# bigbro.net
KiCad netlist of a schematic drawn in EAGLE
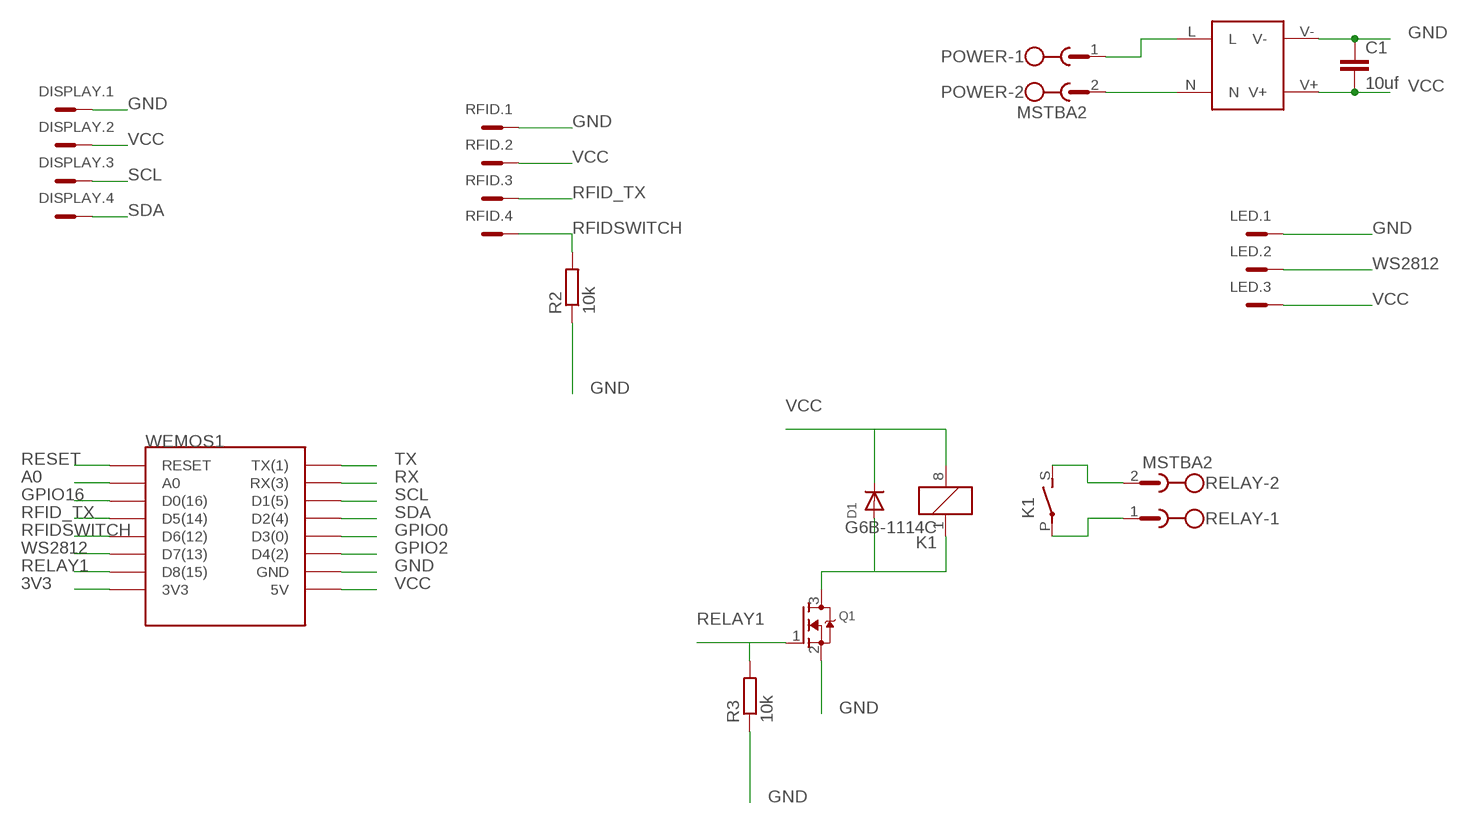
[diagram p0: schematic, sheet 1]

(export (version "E")
  (design (tool "Eeschema 10.0.6"))
  (components
    (comp (ref "C1")
      (value "10uf")
      (footprint "eagle-import:C0805")
      (libsource (lib "eagle-import") (part "C-EUC0805"))
    )
    (comp (ref "D1")
      (value "DIODESMA")
      (footprint "eagle-import:SMADIODE")
      (libsource (lib "eagle-import") (part "DIODESMA"))
    )
    (comp (ref "DISPLAY")
      (value "MC4")
      (footprint "eagle-import:MC4")
      (libsource (lib "eagle-import") (part "MC4"))
    )
    (comp (ref "K1")
      (value "G6B-1114C")
      (footprint "eagle-import:G6B-1114C")
      (libsource (lib "eagle-import") (part "G6B-1114C"))
    )
    (comp (ref "LED")
      (value "MC3")
      (footprint "eagle-import:MC3")
      (libsource (lib "eagle-import") (part "MC3"))
    )
    (comp (ref "POWER")
      (value "MSTBA2")
      (footprint "eagle-import:MSTBA2")
      (fields (field (name "MF") "FARNELL") (field (name "MPN") "1757242"))
      (libsource (lib "eagle-import") (part "MSTBA2"))
    )
    (comp (ref "Q1")
      (value "MOSFET-NREFLOW")
      (footprint "eagle-import:SOT23")
      (libsource (lib "eagle-import") (part "MOSFET-NREFLOW"))
    )
    (comp (ref "R2")
      (value "10k")
      (footprint "eagle-import:M0805")
      (libsource (lib "eagle-import") (part "R-EU_M0805"))
    )
    (comp (ref "R3")
      (value "10k")
      (footprint "eagle-import:M0805")
      (libsource (lib "eagle-import") (part "R-EU_M0805"))
    )
    (comp (ref "RELAY")
      (value "MSTBA2")
      (footprint "eagle-import:MSTBA2")
      (fields (field (name "MF") "FARNELL") (field (name "MPN") "1757242"))
      (libsource (lib "eagle-import") (part "MSTBA2"))
    )
    (comp (ref "RFID")
      (value "MC4")
      (footprint "eagle-import:MC4")
      (libsource (lib "eagle-import") (part "MC4"))
    )
    (comp (ref "U$1")
      (value "HLK-PM03")
      (footprint "eagle-import:HLK-PM03")
      (libsource (lib "eagle-import") (part "HLK-PM03"))
    )
    (comp (ref "WEMOS1")
      (value "WEMOS-D1-MINI")
      (footprint "eagle-import:WEMOS-D1-MINI")
      (libsource (lib "eagle-import") (part "WEMOS-D1-MINI"))
    )
  )
  (nets
    (net (code "1") (name "/3V3") (class "Default")
      (node (ref "WEMOS1") (pin "3V3") (pinfunction "3V3_3V3") (pintype "bidirectional"))
    )
    (net (code "2") (name "/A0") (class "Default")
      (node (ref "WEMOS1") (pin "A0") (pinfunction "A0_A0") (pintype "bidirectional"))
    )
    (net (code "3") (name "/GND") (class "Default")
      (node (ref "C1") (pin "1") (pinfunction "1_1") (pintype "passive"))
      (node (ref "DISPLAY") (pin "1") (pinfunction "SK_1") (pintype "passive"))
      (node (ref "LED") (pin "1") (pinfunction "SK_1") (pintype "passive"))
      (node (ref "Q1") (pin "2") (pinfunction "S_2") (pintype "bidirectional"))
      (node (ref "R2") (pin "1") (pinfunction "1_1") (pintype "passive"))
      (node (ref "R3") (pin "1") (pinfunction "1_1") (pintype "passive"))
      (node (ref "RFID") (pin "1") (pinfunction "SK_1") (pintype "passive"))
      (node (ref "U$1") (pin "V-") (pinfunction "V-_V-") (pintype "bidirectional"))
      (node (ref "WEMOS1") (pin "GND") (pinfunction "GND_GND") (pintype "bidirectional"))
    )
    (net (code "4") (name "/GPIO0") (class "Default")
      (node (ref "WEMOS1") (pin "D3") (pinfunction "D3(0)_D3") (pintype "bidirectional"))
    )
    (net (code "5") (name "/GPIO2") (class "Default")
      (node (ref "WEMOS1") (pin "D4") (pinfunction "D4(2)_D4") (pintype "bidirectional"))
    )
    (net (code "6") (name "/GPIO16") (class "Default")
      (node (ref "WEMOS1") (pin "D0") (pinfunction "D0(16)_D0") (pintype "bidirectional"))
    )
    (net (code "7") (name "/RELAY1") (class "Default")
      (node (ref "Q1") (pin "1") (pinfunction "G_1") (pintype "bidirectional"))
      (node (ref "R3") (pin "2") (pinfunction "2_2") (pintype "passive"))
      (node (ref "WEMOS1") (pin "D8") (pinfunction "D8(15)_D8") (pintype "bidirectional"))
    )
    (net (code "8") (name "/RESET") (class "Default")
      (node (ref "WEMOS1") (pin "RESET") (pinfunction "RESET_RESET") (pintype "bidirectional"))
    )
    (net (code "9") (name "/RFIDSWITCH") (class "Default")
      (node (ref "R2") (pin "2") (pinfunction "2_2") (pintype "passive"))
      (node (ref "RFID") (pin "4") (pinfunction "SK_4") (pintype "passive"))
      (node (ref "WEMOS1") (pin "D6") (pinfunction "D6(12)_D6") (pintype "bidirectional"))
    )
    (net (code "10") (name "/RFID_TX") (class "Default")
      (node (ref "RFID") (pin "3") (pinfunction "SK_3") (pintype "passive"))
      (node (ref "WEMOS1") (pin "D5") (pinfunction "D5(14)_D5") (pintype "bidirectional"))
    )
    (net (code "11") (name "/RX") (class "Default")
      (node (ref "WEMOS1") (pin "RX") (pinfunction "RX(3)_RX") (pintype "bidirectional"))
    )
    (net (code "12") (name "/SCL") (class "Default")
      (node (ref "DISPLAY") (pin "3") (pinfunction "SK_3") (pintype "passive"))
      (node (ref "WEMOS1") (pin "D1") (pinfunction "D1(5)_D1") (pintype "bidirectional"))
    )
    (net (code "13") (name "/SDA") (class "Default")
      (node (ref "DISPLAY") (pin "4") (pinfunction "SK_4") (pintype "passive"))
      (node (ref "WEMOS1") (pin "D2") (pinfunction "D2(4)_D2") (pintype "bidirectional"))
    )
    (net (code "14") (name "/TX") (class "Default")
      (node (ref "WEMOS1") (pin "TX") (pinfunction "TX(1)_TX") (pintype "bidirectional"))
    )
    (net (code "15") (name "/VCC") (class "Default")
      (node (ref "C1") (pin "2") (pinfunction "2_2") (pintype "passive"))
      (node (ref "D1") (pin "C") (pinfunction "C_C") (pintype "passive"))
      (node (ref "DISPLAY") (pin "2") (pinfunction "SK_2") (pintype "passive"))
      (node (ref "K1") (pin "8") (pinfunction "2_8") (pintype "passive"))
      (node (ref "LED") (pin "3") (pinfunction "SK_3") (pintype "passive"))
      (node (ref "RFID") (pin "2") (pinfunction "SK_2") (pintype "passive"))
      (node (ref "U$1") (pin "V+") (pinfunction "V+_V+") (pintype "bidirectional"))
      (node (ref "WEMOS1") (pin "5V") (pinfunction "5V_5V") (pintype "bidirectional"))
    )
    (net (code "16") (name "/WS2812") (class "Default")
      (node (ref "LED") (pin "2") (pinfunction "SK_2") (pintype "passive"))
      (node (ref "WEMOS1") (pin "D7") (pinfunction "D7(13)_D7") (pintype "bidirectional"))
    )
    (net (code "17") (name "Net-(K1-PadP)") (class "Default")
      (node (ref "K1") (pin "P") (pinfunction "P_P") (pintype "passive"))
      (node (ref "RELAY") (pin "1") (pinfunction "1_1") (pintype "passive"))
    )
    (net (code "18") (name "Net-(POWER-Pad1)") (class "Default")
      (node (ref "POWER") (pin "1") (pinfunction "1_1") (pintype "passive"))
      (node (ref "U$1") (pin "L") (pinfunction "L_L") (pintype "bidirectional"))
    )
    (net (code "19") (name "Net-(POWERB-1)") (class "Default")
      (node (ref "POWER") (pin "2") (pinfunction "1_2") (pintype "passive"))
      (node (ref "U$1") (pin "N") (pinfunction "N_N") (pintype "bidirectional"))
    )
    (net (code "20") (name "Net-(Q1-D)") (class "Default")
      (node (ref "D1") (pin "A") (pinfunction "A_A") (pintype "passive"))
      (node (ref "K1") (pin "1") (pinfunction "1_1") (pintype "passive"))
      (node (ref "Q1") (pin "3") (pinfunction "D_3") (pintype "bidirectional"))
    )
    (net (code "21") (name "Net-(RELAYB-1)") (class "Default")
      (node (ref "K1") (pin "S") (pinfunction "S_S") (pintype "passive"))
      (node (ref "RELAY") (pin "2") (pinfunction "1_2") (pintype "passive"))
    )
  )
)
